# IceFeildBoard.net
KiCad netlist of a schematic drawn in EAGLE
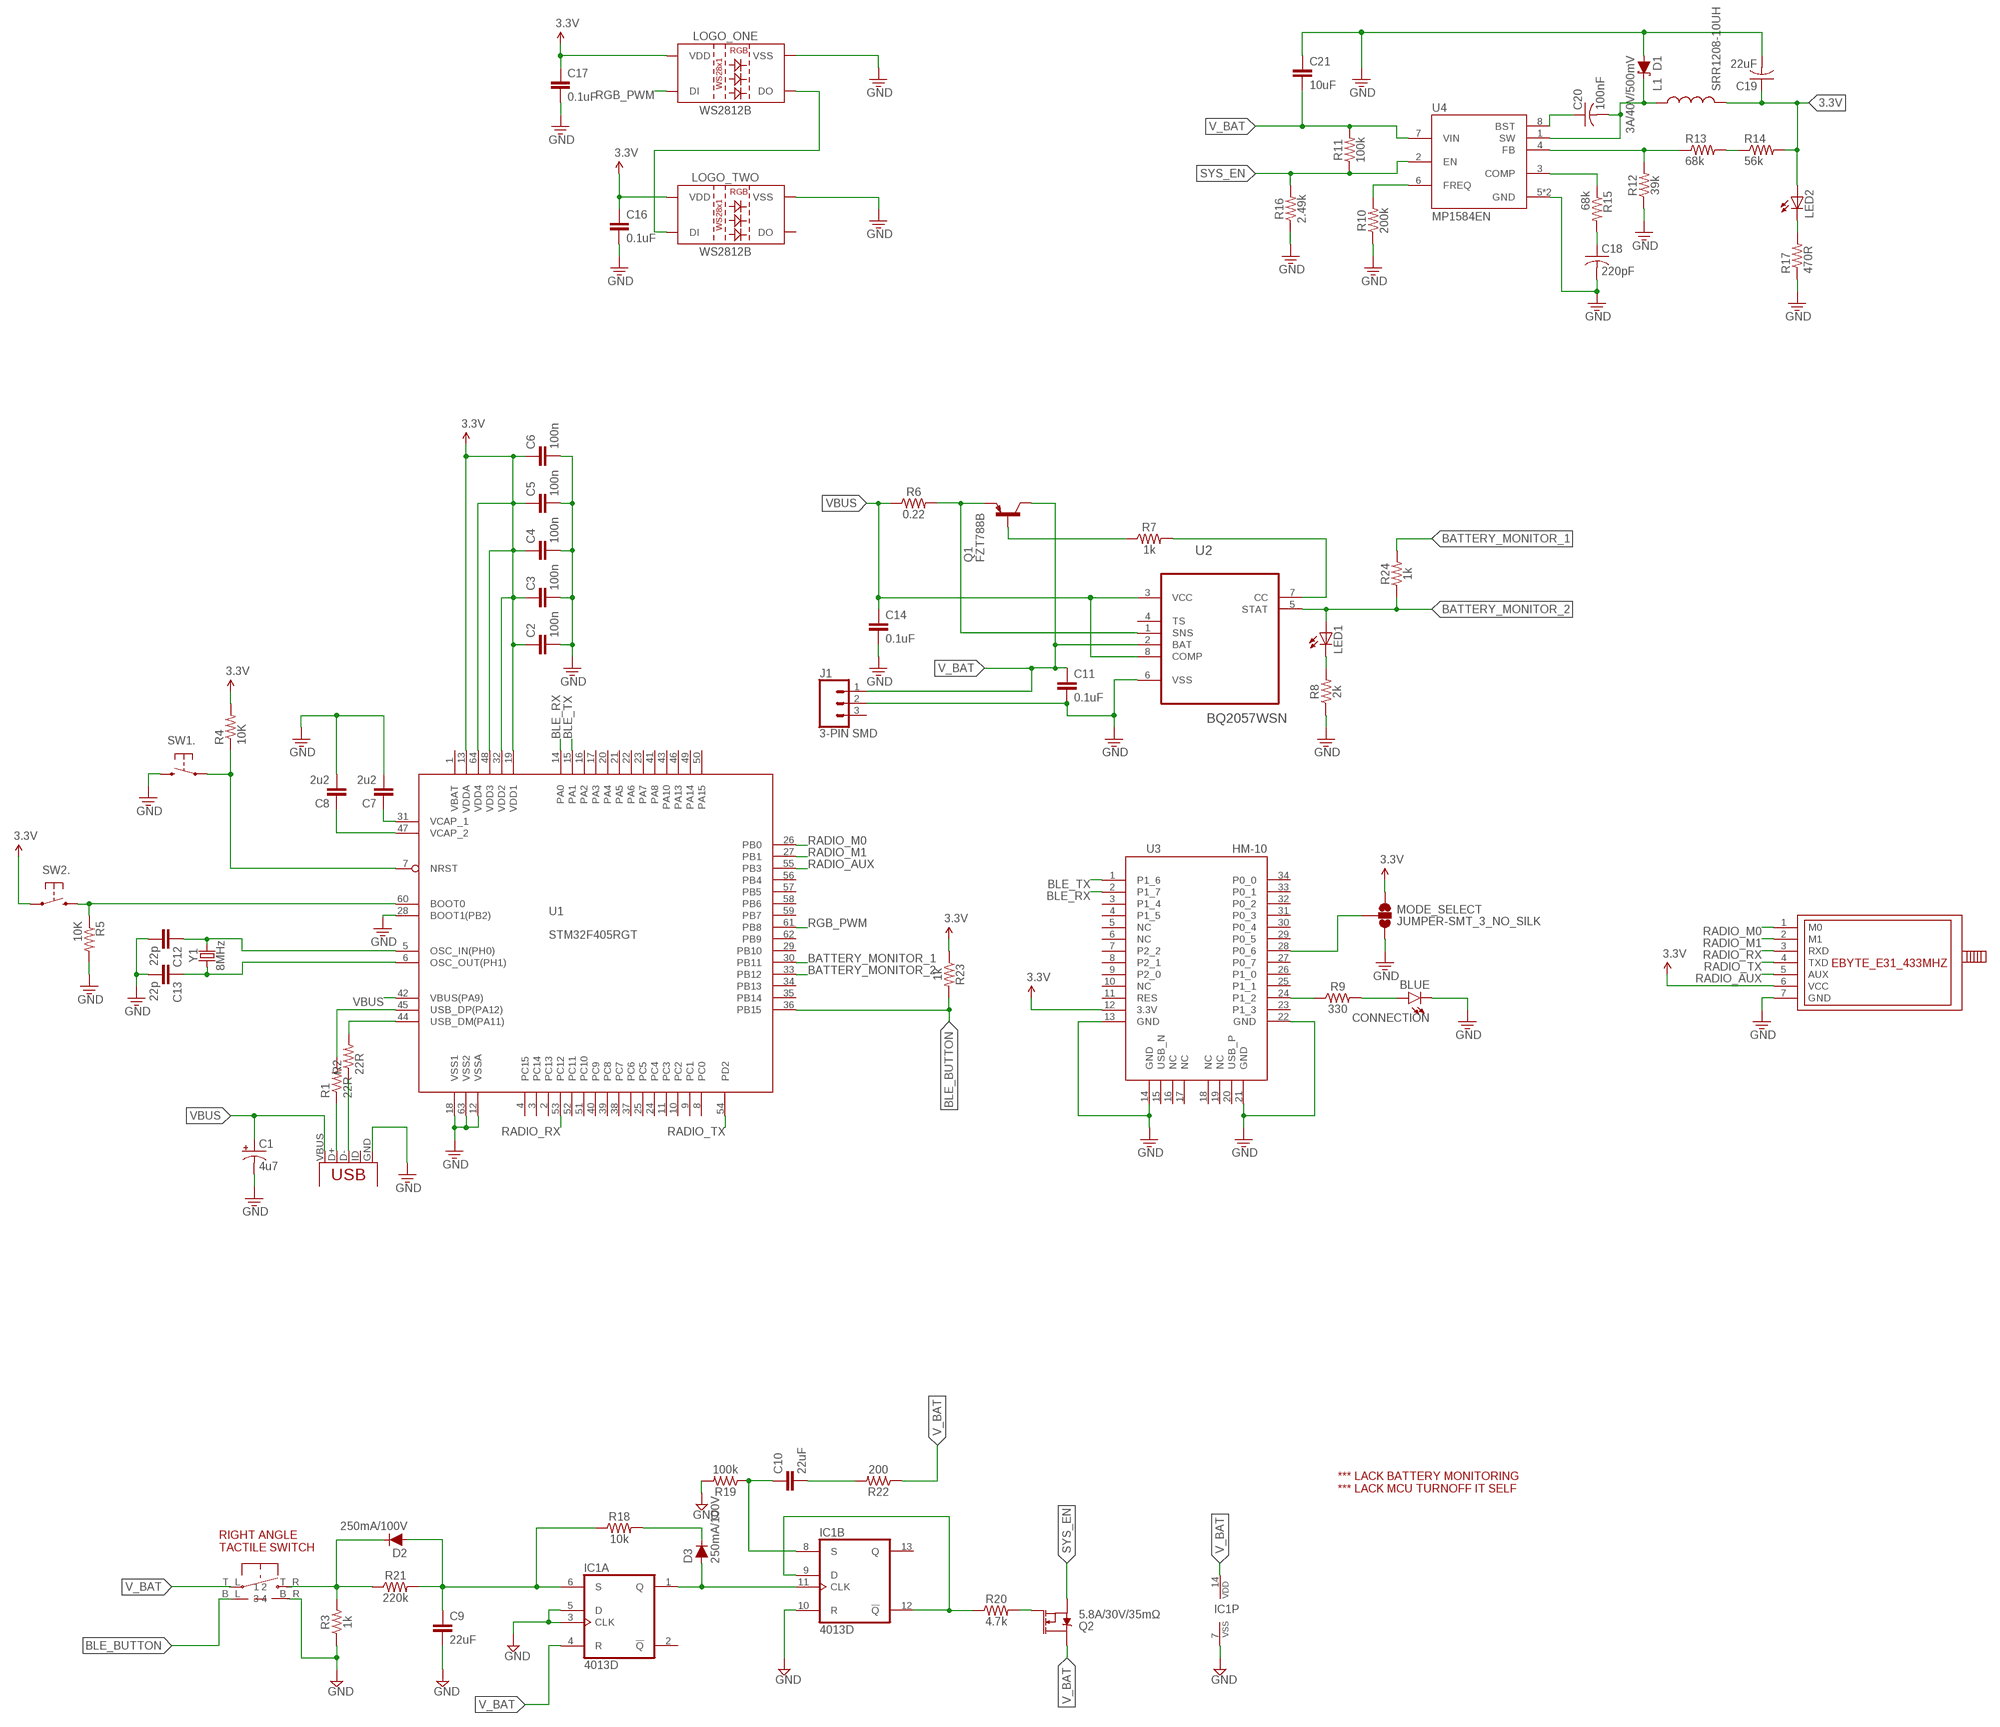
[diagram p0: schematic, sheet 1]

(export (version "E")
  (design (tool "Eeschema 10.0.6"))
  (components
    (comp (ref "C1")
      (value "4u7")
      (footprint "eagle-import:EIA3216-KIT")
      (libsource (lib "eagle-import") (part "CAP_POL1206-KIT"))
    )
    (comp (ref "C2")
      (value "100n")
      (footprint "eagle-import:0603-CAP")
      (libsource (lib "eagle-import") (part "CAP0603-CAP"))
    )
    (comp (ref "C3")
      (value "100n")
      (footprint "eagle-import:0603-CAP")
      (libsource (lib "eagle-import") (part "CAP0603-CAP"))
    )
    (comp (ref "C4")
      (value "100n")
      (footprint "eagle-import:0603-CAP")
      (libsource (lib "eagle-import") (part "CAP0603-CAP"))
    )
    (comp (ref "C5")
      (value "100n")
      (footprint "eagle-import:0603-CAP")
      (libsource (lib "eagle-import") (part "CAP0603-CAP"))
    )
    (comp (ref "C6")
      (value "100n")
      (footprint "eagle-import:0603-CAP")
      (libsource (lib "eagle-import") (part "CAP0603-CAP"))
    )
    (comp (ref "C7")
      (value "2u2")
      (footprint "eagle-import:0603-CAP")
      (libsource (lib "eagle-import") (part "CAP0603-CAP"))
    )
    (comp (ref "C8")
      (value "2u2")
      (footprint "eagle-import:0603-CAP")
      (libsource (lib "eagle-import") (part "CAP0603-CAP"))
    )
    (comp (ref "C9")
      (value "22uF")
      (footprint "eagle-import:0805")
      (libsource (lib "eagle-import") (part "22UF-0805-6.3V-20%"))
    )
    (comp (ref "C10")
      (value "22uF")
      (footprint "eagle-import:0805")
      (libsource (lib "eagle-import") (part "22UF-0805-6.3V-20%"))
    )
    (comp (ref "C11")
      (value "0.1uF")
      (footprint "eagle-import:0603")
      (libsource (lib "eagle-import") (part "0.1UF-0603-25V-(+80/-20%)"))
    )
    (comp (ref "C12")
      (value "22p")
      (footprint "eagle-import:0603-CAP")
      (libsource (lib "eagle-import") (part "CAP0603-CAP"))
    )
    (comp (ref "C13")
      (value "22p")
      (footprint "eagle-import:0603-CAP")
      (libsource (lib "eagle-import") (part "CAP0603-CAP"))
    )
    (comp (ref "C14")
      (value "0.1uF")
      (footprint "eagle-import:0603")
      (libsource (lib "eagle-import") (part "0.1UF-0603-25V-(+80/-20%)"))
    )
    (comp (ref "C16")
      (value "0.1uF")
      (footprint "eagle-import:0603")
      (libsource (lib "eagle-import") (part "0.1UF-0603-25V-5%"))
    )
    (comp (ref "C17")
      (value "0.1uF")
      (footprint "eagle-import:0603")
      (libsource (lib "eagle-import") (part "0.1UF-0603-25V-5%"))
    )
    (comp (ref "C18")
      (value "220pF")
      (footprint "eagle-import:C0603")
      (libsource (lib "eagle-import") (part "C-USC0603"))
    )
    (comp (ref "C19")
      (value "22uF")
      (footprint "eagle-import:C0603")
      (libsource (lib "eagle-import") (part "C-USC0603"))
    )
    (comp (ref "C20")
      (value "100nF")
      (footprint "eagle-import:C0603")
      (libsource (lib "eagle-import") (part "C-USC0603"))
    )
    (comp (ref "C21")
      (value "10uF")
      (footprint "eagle-import:0603")
      (libsource (lib "eagle-import") (part "10UF-0603-6.3V-20%"))
    )
    (comp (ref "CONNECTION")
      (value "BLUE")
      (footprint "eagle-import:LED-0603")
      (libsource (lib "eagle-import") (part "LED-BLUE0603"))
    )
    (comp (ref "D1")
      (value "3A/40V/500mV")
      (footprint "eagle-import:SMA-DIODE")
      (libsource (lib "eagle-import") (part "DIODE-SCHOTTKY-B340A"))
    )
    (comp (ref "D2")
      (value "250mA/100V")
      (footprint "eagle-import:SOD-323")
      (libsource (lib "eagle-import") (part "DIODE-BAS16J"))
    )
    (comp (ref "D3")
      (value "250mA/100V")
      (footprint "eagle-import:SOD-323")
      (libsource (lib "eagle-import") (part "DIODE-BAS16J"))
    )
    (comp (ref "IC1")
      (value "4013D")
      (footprint "eagle-import:SO14")
      (fields (field (name "OC_NEWARK") "unknown"))
      (libsource (lib "eagle-import") (part "4013D"))
    )
    (comp (ref "J1")
      (value "3-PIN SMD")
      (footprint "eagle-import:JST-3-SMD")
      (libsource (lib "eagle-import") (part "CONN_03JST-SMD"))
    )
    (comp (ref "L1")
      (value "SRR1208-10UH")
      (footprint "eagle-import:1008")
      (libsource (lib "eagle-import") (part "SRR1208-10UH"))
    )
    (comp (ref "LED1")
      (value "LED0603")
      (footprint "eagle-import:LED-0603")
      (libsource (lib "eagle-import") (part "LED0603"))
    )
    (comp (ref "LED2")
      (value "LED0603")
      (footprint "eagle-import:LED-0603")
      (libsource (lib "eagle-import") (part "LED0603"))
    )
    (comp (ref "LOGO_ONE")
      (value "WS2812B")
      (footprint "eagle-import:WS2812B")
      (libsource (lib "eagle-import") (part "WS2812B"))
    )
    (comp (ref "LOGO_TWO")
      (value "WS2812B")
      (footprint "eagle-import:WS2812B")
      (libsource (lib "eagle-import") (part "WS2812B"))
    )
    (comp (ref "MODE_SELECT")
      (value "JUMPER-SMT_3_NO_SILK")
      (footprint "eagle-import:SMT-JUMPER_3_NO_SILK")
      (libsource (lib "eagle-import") (part "JUMPER-SMT_3_NO_SILK"))
    )
    (comp (ref "Q1")
      (value "FZT788B")
      (footprint "eagle-import:SOT230P700X180-4N")
      (libsource (lib "eagle-import") (part "FZT788B"))
    )
    (comp (ref "Q2")
      (value "5.8A/30V/35mΩ")
      (footprint "eagle-import:SOT23-3")
      (libsource (lib "eagle-import") (part "MOSFET-NCH-AO3404A"))
    )
    (comp (ref "R1")
      (value "22R")
      (footprint "eagle-import:0603-RES")
      (libsource (lib "eagle-import") (part "RESISTOR0603-RES"))
    )
    (comp (ref "R2")
      (value "22R")
      (footprint "eagle-import:0603-RES")
      (libsource (lib "eagle-import") (part "RESISTOR0603-RES"))
    )
    (comp (ref "R3")
      (value "1k")
      (footprint "eagle-import:0603")
      (libsource (lib "eagle-import") (part "1KOHM-0603-1/10W-1%"))
    )
    (comp (ref "R4")
      (value "10K")
      (footprint "eagle-import:0603-RES")
      (libsource (lib "eagle-import") (part "RESISTOR0603-RES"))
    )
    (comp (ref "R5")
      (value "10K")
      (footprint "eagle-import:0603-RES")
      (libsource (lib "eagle-import") (part "RESISTOR0603-RES"))
    )
    (comp (ref "R6")
      (value "0.22")
      (footprint "eagle-import:0805")
      (libsource (lib "eagle-import") (part "0.22OHM-0805-1/4W-1%"))
    )
    (comp (ref "R7")
      (value "1k")
      (footprint "eagle-import:0603")
      (libsource (lib "eagle-import") (part "1KOHM-0603-1/10W-1%"))
    )
    (comp (ref "R8")
      (value "2k")
      (footprint "eagle-import:0603")
      (libsource (lib "eagle-import") (part "RESISTOR0603"))
    )
    (comp (ref "R9")
      (value "330")
      (footprint "eagle-import:0603")
      (libsource (lib "eagle-import") (part "330OHM-0603-1/10W-1%"))
    )
    (comp (ref "R10")
      (value "200k")
      (footprint "eagle-import:0603")
      (libsource (lib "eagle-import") (part "200KOHM-0603-1/10W-1%"))
    )
    (comp (ref "R11")
      (value "100k")
      (footprint "eagle-import:0603")
      (libsource (lib "eagle-import") (part "100KOHM-0603-1/10W-1%"))
    )
    (comp (ref "R12")
      (value "39k")
      (footprint "eagle-import:0603")
      (libsource (lib "eagle-import") (part "39KOHM-0603-1/10W-1%"))
    )
    (comp (ref "R13")
      (value "68k")
      (footprint "eagle-import:R0603")
      (libsource (lib "eagle-import") (part "R-US_R0603"))
    )
    (comp (ref "R14")
      (value "56k")
      (footprint "eagle-import:R0603")
      (libsource (lib "eagle-import") (part "R-US_R0603"))
    )
    (comp (ref "R15")
      (value "68k")
      (footprint "eagle-import:R0603")
      (libsource (lib "eagle-import") (part "R-US_R0603"))
    )
    (comp (ref "R16")
      (value "2.49k")
      (footprint "eagle-import:0603")
      (libsource (lib "eagle-import") (part "2.49KOHM-0603-1/10W-1%"))
    )
    (comp (ref "R17")
      (value "470R")
      (footprint "eagle-import:0603-RES")
      (libsource (lib "eagle-import") (part "RESISTOR0603-RES"))
    )
    (comp (ref "R18")
      (value "10k")
      (footprint "eagle-import:0603")
      (libsource (lib "eagle-import") (part "10KOHM-0603-1/10W-1%"))
    )
    (comp (ref "R19")
      (value "100k")
      (footprint "eagle-import:0603")
      (libsource (lib "eagle-import") (part "100KOHM-0603-1/10W-1%"))
    )
    (comp (ref "R20")
      (value "4.7k")
      (footprint "eagle-import:0603")
      (libsource (lib "eagle-import") (part "4.7KOHM-0603-1/10W-1%"))
    )
    (comp (ref "R21")
      (value "220k")
      (footprint "eagle-import:0603")
      (libsource (lib "eagle-import") (part "220KOHM-0603-1/10W-1%"))
    )
    (comp (ref "R22")
      (value "200")
      (footprint "eagle-import:0603")
      (libsource (lib "eagle-import") (part "200OHM-0603-1/10W-1%"))
    )
    (comp (ref "R23")
      (value "1k")
      (footprint "eagle-import:0603")
      (libsource (lib "eagle-import") (part "1KOHM-0603-1/10W-1%"))
    )
    (comp (ref "R24")
      (value "1k")
      (footprint "eagle-import:0603")
      (libsource (lib "eagle-import") (part "1KOHM-0603-1/10W-1%"))
    )
    (comp (ref "SW1")
      (value "!RST")
      (footprint "eagle-import:SWITCH-TACT-B3U-1100P-B")
      (libsource (lib "eagle-import") (part "SWITCH-B3U-1110-BOSS"))
    )
    (comp (ref "SW2")
      (value "BOOT")
      (footprint "eagle-import:SWITCH-TACT-B3U-1100P-B")
      (libsource (lib "eagle-import") (part "SWITCH-B3U-1110-BOSS"))
    )
    (comp (ref "U$1")
      (value "RIGHT_ANGLE_TACTILE_SWITCH")
      (footprint "eagle-import:RIGHT_ANGLE_TACTILE_SWITCH")
      (libsource (lib "eagle-import") (part "RIGHT_ANGLE_TACTILE_SWITCH"))
    )
    (comp (ref "U$2")
      (value "EBYTE_E31_433MHZ")
      (footprint "eagle-import:EBYTE_E31_433MHZ")
      (libsource (lib "eagle-import") (part "EBYTE_E31_433MHZ"))
    )
    (comp (ref "U1")
      (value "STM32F405RGT")
      (footprint "eagle-import:LQFP64")
      (libsource (lib "eagle-import") (part "STM32F405RGT"))
    )
    (comp (ref "U2")
      (value "BQ2057WSN")
      (footprint "eagle-import:SOIC127P600X175-8N")
      (fields (field (name "MF") "Texas Instruments"))
      (libsource (lib "eagle-import") (part "BQ2057WSN"))
    )
    (comp (ref "U3")
      (value "HM-10")
      (footprint "eagle-import:HM-10")
      (libsource (lib "eagle-import") (part "HM-10"))
    )
    (comp (ref "U4")
      (value "MP1584EN")
      (footprint "eagle-import:SOIC9P127_490X600X170L84X42T330X241N")
      (fields (field (name "MF") "Monolithic Power Systems"))
      (libsource (lib "eagle-import") (part "MP1584EN"))
    )
    (comp (ref "USB")
      (value "USB-MICROB-SMD")
      (footprint "eagle-import:USB-MICROB-SMD")
      (libsource (lib "eagle-import") (part "USB-MICROB-SMD"))
    )
    (comp (ref "Y1")
      (value "8MHz")
      (footprint "eagle-import:CRYSTAL-SMD-5X3.2-4PAD")
      (libsource (lib "eagle-import") (part "CRYSTAL-8MHZSMD-5X3.2"))
    )
  )
  (nets
    (net (code "1") (name "/BLE_RX") (class "Default")
      (node (ref "U1") (pin "14") (pinfunction "PA0_14") (pintype "bidirectional"))
      (node (ref "U3") (pin "2") (pinfunction "P1_7_2") (pintype "bidirectional"))
    )
    (net (code "2") (name "/BLE_TX") (class "Default")
      (node (ref "U1") (pin "15") (pinfunction "PA1_15") (pintype "bidirectional"))
      (node (ref "U3") (pin "1") (pinfunction "P1_6_1") (pintype "bidirectional"))
    )
    (net (code "3") (name "/RADIO_AUX") (class "Default")
      (node (ref "U$2") (pin "5") (pinfunction "AUX_5") (pintype "bidirectional"))
      (node (ref "U1") (pin "55") (pinfunction "PB3_55") (pintype "bidirectional"))
    )
    (net (code "4") (name "/RADIO_M0") (class "Default")
      (node (ref "U$2") (pin "1") (pinfunction "M0_1") (pintype "bidirectional"))
      (node (ref "U1") (pin "26") (pinfunction "PB0_26") (pintype "bidirectional"))
    )
    (net (code "5") (name "/RADIO_M1") (class "Default")
      (node (ref "U$2") (pin "2") (pinfunction "M1_2") (pintype "bidirectional"))
      (node (ref "U1") (pin "27") (pinfunction "PB1_27") (pintype "bidirectional"))
    )
    (net (code "6") (name "/RADIO_RX") (class "Default")
      (node (ref "U$2") (pin "3") (pinfunction "RXD_3") (pintype "bidirectional"))
      (node (ref "U1") (pin "53") (pinfunction "PC12_53") (pintype "bidirectional"))
    )
    (net (code "7") (name "/RADIO_TX") (class "Default")
      (node (ref "U$2") (pin "4") (pinfunction "TXD_4") (pintype "bidirectional"))
      (node (ref "U1") (pin "54") (pinfunction "PD2_54") (pintype "bidirectional"))
    )
    (net (code "8") (name "/RGB_PWM") (class "Default")
      (node (ref "LOGO_ONE") (pin "4") (pinfunction "DI_4") (pintype "bidirectional"))
      (node (ref "U1") (pin "61") (pinfunction "PB8_61") (pintype "bidirectional"))
    )
    (net (code "9") (name "/VBAT") (class "Default")
      (node (ref "U1") (pin "1") (pinfunction "VBAT_1") (pintype "power_in"))
    )
    (net (code "10") (name "3.3V") (class "Default")
      (node (ref "C16") (pin "1") (pinfunction "1_1") (pintype "passive"))
      (node (ref "C17") (pin "1") (pinfunction "1_1") (pintype "passive"))
      (node (ref "C19") (pin "1") (pinfunction "1_1") (pintype "passive"))
      (node (ref "C2") (pin "1") (pinfunction "1_1") (pintype "passive"))
      (node (ref "C3") (pin "1") (pinfunction "1_1") (pintype "passive"))
      (node (ref "C4") (pin "1") (pinfunction "1_1") (pintype "passive"))
      (node (ref "C5") (pin "1") (pinfunction "1_1") (pintype "passive"))
      (node (ref "C6") (pin "1") (pinfunction "1_1") (pintype "passive"))
      (node (ref "L1") (pin "2") (pinfunction "2_2") (pintype "passive"))
      (node (ref "LED2") (pin "A") (pinfunction "A_A") (pintype "passive"))
      (node (ref "LOGO_ONE") (pin "1") (pinfunction "VDD_1") (pintype "bidirectional"))
      (node (ref "LOGO_TWO") (pin "1") (pinfunction "VDD_1") (pintype "bidirectional"))
      (node (ref "MODE_SELECT") (pin "1") (pinfunction "1_1") (pintype "passive"))
      (node (ref "R14") (pin "2") (pinfunction "2_2") (pintype "passive"))
      (node (ref "R23") (pin "1") (pinfunction "1_1") (pintype "passive"))
      (node (ref "R4") (pin "2") (pinfunction "2_2") (pintype "passive"))
      (node (ref "SW2") (pin "1") (pinfunction "1_1") (pintype "passive"))
      (node (ref "U$2") (pin "6") (pinfunction "VCC_6") (pintype "bidirectional"))
      (node (ref "U1") (pin "13") (pinfunction "VDDA_13") (pintype "power_in"))
      (node (ref "U1") (pin "19") (pinfunction "VDD1_19") (pintype "power_in"))
      (node (ref "U1") (pin "32") (pinfunction "VDD2_32") (pintype "power_in"))
      (node (ref "U1") (pin "48") (pinfunction "VDD3_48") (pintype "power_in"))
      (node (ref "U1") (pin "64") (pinfunction "VDD4_64") (pintype "power_in"))
      (node (ref "U3") (pin "12") (pinfunction "3.3V_12") (pintype "bidirectional"))
    )
    (net (code "11") (name "BATTERY_MONITOR_1") (class "Default")
      (node (ref "R24") (pin "2") (pinfunction "2_2") (pintype "passive"))
      (node (ref "U1") (pin "30") (pinfunction "PB11_30") (pintype "bidirectional"))
    )
    (net (code "12") (name "BATTERY_MONITOR_2") (class "Default")
      (node (ref "LED1") (pin "A") (pinfunction "A_A") (pintype "passive"))
      (node (ref "R24") (pin "1") (pinfunction "1_1") (pintype "passive"))
      (node (ref "U1") (pin "33") (pinfunction "PB12_33") (pintype "bidirectional"))
      (node (ref "U2") (pin "5") (pinfunction "STAT_5") (pintype "output"))
    )
    (net (code "13") (name "BLE_BUTTON") (class "Default")
      (node (ref "R23") (pin "2") (pinfunction "2_2") (pintype "passive"))
      (node (ref "U$1") (pin "B_L") (pinfunction "3_B_L") (pintype "bidirectional"))
      (node (ref "U1") (pin "36") (pinfunction "PB15_36") (pintype "bidirectional"))
    )
    (net (code "14") (name "GND") (class "Default")
      (node (ref "C1") (pin "C") (pinfunction "-_C") (pintype "passive"))
      (node (ref "C11") (pin "2") (pinfunction "2_2") (pintype "passive"))
      (node (ref "C12") (pin "2") (pinfunction "2_2") (pintype "passive"))
      (node (ref "C13") (pin "2") (pinfunction "2_2") (pintype "passive"))
      (node (ref "C14") (pin "2") (pinfunction "2_2") (pintype "passive"))
      (node (ref "C16") (pin "2") (pinfunction "2_2") (pintype "passive"))
      (node (ref "C17") (pin "2") (pinfunction "2_2") (pintype "passive"))
      (node (ref "C18") (pin "2") (pinfunction "2_2") (pintype "passive"))
      (node (ref "C19") (pin "2") (pinfunction "2_2") (pintype "passive"))
      (node (ref "C2") (pin "2") (pinfunction "2_2") (pintype "passive"))
      (node (ref "C21") (pin "1") (pinfunction "1_1") (pintype "passive"))
      (node (ref "C3") (pin "2") (pinfunction "2_2") (pintype "passive"))
      (node (ref "C4") (pin "2") (pinfunction "2_2") (pintype "passive"))
      (node (ref "C5") (pin "2") (pinfunction "2_2") (pintype "passive"))
      (node (ref "C6") (pin "2") (pinfunction "2_2") (pintype "passive"))
      (node (ref "C7") (pin "2") (pinfunction "2_2") (pintype "passive"))
      (node (ref "C8") (pin "2") (pinfunction "2_2") (pintype "passive"))
      (node (ref "C9") (pin "2") (pinfunction "2_2") (pintype "passive"))
      (node (ref "CONNECTION") (pin "C") (pinfunction "C_C") (pintype "passive"))
      (node (ref "D1") (pin "A") (pinfunction "A_A") (pintype "passive"))
      (node (ref "IC1") (pin "10") (pinfunction "R_10") (pintype "input"))
      (node (ref "IC1") (pin "3") (pinfunction "CLK_3") (pintype "input"))
      (node (ref "IC1") (pin "5") (pinfunction "D_5") (pintype "input"))
      (node (ref "IC1") (pin "7") (pinfunction "VSS_7") (pintype "power_in"))
      (node (ref "J1") (pin "2") (pinfunction "2_2") (pintype "passive"))
      (node (ref "LOGO_ONE") (pin "3") (pinfunction "VSS_3") (pintype "bidirectional"))
      (node (ref "LOGO_TWO") (pin "3") (pinfunction "VSS_3") (pintype "bidirectional"))
      (node (ref "MODE_SELECT") (pin "3") (pinfunction "3_3") (pintype "passive"))
      (node (ref "R10") (pin "1") (pinfunction "1_1") (pintype "passive"))
      (node (ref "R12") (pin "1") (pinfunction "1_1") (pintype "passive"))
      (node (ref "R16") (pin "1") (pinfunction "1_1") (pintype "passive"))
      (node (ref "R17") (pin "1") (pinfunction "1_1") (pintype "passive"))
      (node (ref "R19") (pin "2") (pinfunction "2_2") (pintype "passive"))
      (node (ref "R3") (pin "1") (pinfunction "1_1") (pintype "passive"))
      (node (ref "R5") (pin "2") (pinfunction "2_2") (pintype "passive"))
      (node (ref "R8") (pin "1") (pinfunction "1_1") (pintype "passive"))
      (node (ref "SW1") (pin "2") (pinfunction "2_2") (pintype "passive"))
      (node (ref "U$1") (pin "B_R") (pinfunction "4_B_R") (pintype "bidirectional"))
      (node (ref "U$2") (pin "7") (pinfunction "GND_7") (pintype "bidirectional"))
      (node (ref "U1") (pin "12") (pinfunction "VSSA_12") (pintype "power_in"))
      (node (ref "U1") (pin "18") (pinfunction "VSS1_18") (pintype "power_in"))
      (node (ref "U1") (pin "28") (pinfunction "BOOT1(PB2)_28") (pintype "input"))
      (node (ref "U1") (pin "63") (pinfunction "VSS2_63") (pintype "power_in"))
      (node (ref "U2") (pin "6") (pinfunction "VSS_6") (pintype "power_in"))
      (node (ref "U3") (pin "13") (pinfunction "GND_13") (pintype "bidirectional"))
      (node (ref "U3") (pin "14") (pinfunction "GND_14") (pintype "bidirectional"))
      (node (ref "U3") (pin "21") (pinfunction "GND_21") (pintype "bidirectional"))
      (node (ref "U3") (pin "22") (pinfunction "GND_22") (pintype "bidirectional"))
      (node (ref "U4") (pin "5") (pinfunction "GND_5") (pintype "power_in"))
      (node (ref "U4") (pin "9") (pinfunction "GND_9") (pintype "power_in"))
      (node (ref "USB") (pin "GND") (pinfunction "GND_GND") (pintype "bidirectional"))
    )
    (net (code "15") (name "Net-(C10-Pad2)") (class "Default")
      (node (ref "C10") (pin "2") (pinfunction "2_2") (pintype "passive"))
      (node (ref "R22") (pin "2") (pinfunction "2_2") (pintype "passive"))
    )
    (net (code "16") (name "Net-(C18-Pad1)") (class "Default")
      (node (ref "C18") (pin "1") (pinfunction "1_1") (pintype "passive"))
      (node (ref "R15") (pin "2") (pinfunction "2_2") (pintype "passive"))
    )
    (net (code "17") (name "Net-(CONNECTION-PadA)") (class "Default")
      (node (ref "CONNECTION") (pin "A") (pinfunction "A_A") (pintype "passive"))
      (node (ref "R9") (pin "2") (pinfunction "2_2") (pintype "passive"))
    )
    (net (code "18") (name "Net-(D3-PadC)") (class "Default")
      (node (ref "D3") (pin "C") (pinfunction "C_C") (pintype "passive"))
      (node (ref "R18") (pin "2") (pinfunction "2_2") (pintype "passive"))
    )
    (net (code "19") (name "Net-(IC1A-Q)") (class "Default")
      (node (ref "D3") (pin "A") (pinfunction "A_A") (pintype "passive"))
      (node (ref "IC1") (pin "1") (pinfunction "Q_1") (pintype "output"))
      (node (ref "IC1") (pin "11") (pinfunction "CLK_11") (pintype "input"))
    )
    (net (code "20") (name "Net-(IC1A-S)") (class "Default")
      (node (ref "C9") (pin "1") (pinfunction "1_1") (pintype "passive"))
      (node (ref "D2") (pin "A") (pinfunction "A_A") (pintype "passive"))
      (node (ref "IC1") (pin "6") (pinfunction "S_6") (pintype "input"))
      (node (ref "R18") (pin "1") (pinfunction "1_1") (pintype "passive"))
      (node (ref "R21") (pin "2") (pinfunction "2_2") (pintype "passive"))
    )
    (net (code "21") (name "Net-(IC1B-D)") (class "Default")
      (node (ref "IC1") (pin "12") (pinfunction "~{Q}_12") (pintype "output"))
      (node (ref "IC1") (pin "9") (pinfunction "D_9") (pintype "input"))
      (node (ref "R20") (pin "1") (pinfunction "1_1") (pintype "passive"))
    )
    (net (code "22") (name "Net-(IC1B-S)") (class "Default")
      (node (ref "C10") (pin "1") (pinfunction "1_1") (pintype "passive"))
      (node (ref "IC1") (pin "8") (pinfunction "S_8") (pintype "input"))
      (node (ref "R19") (pin "1") (pinfunction "1_1") (pintype "passive"))
    )
    (net (code "23") (name "Net-(LED1-PadC)") (class "Default")
      (node (ref "LED1") (pin "C") (pinfunction "C_C") (pintype "passive"))
      (node (ref "R8") (pin "2") (pinfunction "2_2") (pintype "passive"))
    )
    (net (code "24") (name "Net-(LED2-PadC)") (class "Default")
      (node (ref "LED2") (pin "C") (pinfunction "C_C") (pintype "passive"))
      (node (ref "R17") (pin "2") (pinfunction "2_2") (pintype "passive"))
    )
    (net (code "25") (name "Net-(LOGO_ONE-DO)") (class "Default")
      (node (ref "LOGO_ONE") (pin "2") (pinfunction "DO_2") (pintype "bidirectional"))
      (node (ref "LOGO_TWO") (pin "4") (pinfunction "DI_4") (pintype "bidirectional"))
    )
    (net (code "26") (name "Net-(Q1-B)") (class "Default")
      (node (ref "Q1") (pin "1") (pinfunction "B_1") (pintype "passive"))
      (node (ref "R7") (pin "1") (pinfunction "1_1") (pintype "passive"))
    )
    (net (code "27") (name "Net-(Q1-E)") (class "Default")
      (node (ref "Q1") (pin "3") (pinfunction "E_3") (pintype "passive"))
      (node (ref "R6") (pin "2") (pinfunction "2_2") (pintype "passive"))
      (node (ref "U2") (pin "1") (pinfunction "SNS_1") (pintype "input"))
    )
    (net (code "28") (name "Net-(Q2-G)") (class "Default")
      (node (ref "Q2") (pin "1") (pinfunction "G_1") (pintype "bidirectional"))
      (node (ref "R20") (pin "2") (pinfunction "2_2") (pintype "passive"))
    )
    (net (code "29") (name "Net-(R1-Pad1)") (class "Default")
      (node (ref "R1") (pin "1") (pinfunction "1_1") (pintype "passive"))
      (node (ref "USB") (pin "D+") (pinfunction "D+_D+") (pintype "bidirectional"))
    )
    (net (code "30") (name "Net-(R2-Pad1)") (class "Default")
      (node (ref "R2") (pin "1") (pinfunction "1_1") (pintype "passive"))
      (node (ref "USB") (pin "D-") (pinfunction "D-_D-") (pintype "bidirectional"))
    )
    (net (code "31") (name "Net-(R13-Pad2)") (class "Default")
      (node (ref "R13") (pin "2") (pinfunction "2_2") (pintype "passive"))
      (node (ref "R14") (pin "1") (pinfunction "1_1") (pintype "passive"))
    )
    (net (code "32") (name "Net-(U$1-2)") (class "Default")
      (node (ref "D2") (pin "C") (pinfunction "C_C") (pintype "passive"))
      (node (ref "R21") (pin "1") (pinfunction "1_1") (pintype "passive"))
      (node (ref "R3") (pin "2") (pinfunction "2_2") (pintype "passive"))
      (node (ref "U$1") (pin "T_R") (pinfunction "2_T_R") (pintype "bidirectional"))
    )
    (net (code "33") (name "Net-(U1-BOOT0)") (class "Default")
      (node (ref "R5") (pin "1") (pinfunction "1_1") (pintype "passive"))
      (node (ref "SW2") (pin "2") (pinfunction "2_2") (pintype "passive"))
      (node (ref "U1") (pin "60") (pinfunction "BOOT0_60") (pintype "input"))
    )
    (net (code "34") (name "Net-(U1-NRST)") (class "Default")
      (node (ref "R4") (pin "1") (pinfunction "1_1") (pintype "passive"))
      (node (ref "SW1") (pin "1") (pinfunction "1_1") (pintype "passive"))
      (node (ref "U1") (pin "7") (pinfunction "NRST_7") (pintype "input"))
    )
    (net (code "35") (name "Net-(U1-OSC_IN(PH0))") (class "Default")
      (node (ref "C12") (pin "1") (pinfunction "1_1") (pintype "passive"))
      (node (ref "U1") (pin "5") (pinfunction "OSC_IN(PH0)_5") (pintype "bidirectional"))
      (node (ref "Y1") (pin "3") (pinfunction "2_3") (pintype "passive"))
    )
    (net (code "36") (name "Net-(U1-OSC_OUT(PH1))") (class "Default")
      (node (ref "C13") (pin "1") (pinfunction "1_1") (pintype "passive"))
      (node (ref "U1") (pin "6") (pinfunction "OSC_OUT(PH1)_6") (pintype "bidirectional"))
      (node (ref "Y1") (pin "1") (pinfunction "1_1") (pintype "passive"))
    )
    (net (code "37") (name "Net-(U1-USB_DM(PA11))") (class "Default")
      (node (ref "R2") (pin "2") (pinfunction "2_2") (pintype "passive"))
      (node (ref "U1") (pin "44") (pinfunction "USB_DM(PA11)_44") (pintype "bidirectional"))
    )
    (net (code "38") (name "Net-(U1-USB_DP(PA12))") (class "Default")
      (node (ref "R1") (pin "2") (pinfunction "2_2") (pintype "passive"))
      (node (ref "U1") (pin "45") (pinfunction "USB_DP(PA12)_45") (pintype "bidirectional"))
    )
    (net (code "39") (name "Net-(U1-VCAP_1)") (class "Default")
      (node (ref "C7") (pin "1") (pinfunction "1_1") (pintype "passive"))
      (node (ref "U1") (pin "31") (pinfunction "VCAP_1_31") (pintype "bidirectional"))
    )
    (net (code "40") (name "Net-(U1-VCAP_2)") (class "Default")
      (node (ref "C8") (pin "1") (pinfunction "1_1") (pintype "passive"))
      (node (ref "U1") (pin "47") (pinfunction "VCAP_2_47") (pintype "bidirectional"))
    )
    (net (code "41") (name "Net-(U2-CC)") (class "Default")
      (node (ref "R7") (pin "2") (pinfunction "2_2") (pintype "passive"))
      (node (ref "U2") (pin "7") (pinfunction "CC_7") (pintype "output"))
    )
    (net (code "42") (name "Net-(U2-COMP)") (class "Default")
      (node (ref "C14") (pin "1") (pinfunction "1_1") (pintype "passive"))
      (node (ref "R6") (pin "1") (pinfunction "1_1") (pintype "passive"))
      (node (ref "U2") (pin "3") (pinfunction "VCC_3") (pintype "power_in"))
      (node (ref "U2") (pin "8") (pinfunction "COMP_8") (pintype "input"))
    )
    (net (code "43") (name "Net-(U3-P0_6)") (class "Default")
      (node (ref "MODE_SELECT") (pin "2") (pinfunction "2_2") (pintype "passive"))
      (node (ref "U3") (pin "28") (pinfunction "P0_6_28") (pintype "bidirectional"))
    )
    (net (code "44") (name "Net-(U3-P1_2)") (class "Default")
      (node (ref "R9") (pin "1") (pinfunction "1_1") (pintype "passive"))
      (node (ref "U3") (pin "24") (pinfunction "P1_2_24") (pintype "bidirectional"))
    )
    (net (code "45") (name "Net-(U4-BST)") (class "Default")
      (node (ref "C20") (pin "1") (pinfunction "1_1") (pintype "passive"))
      (node (ref "U4") (pin "8") (pinfunction "BST_8") (pintype "passive"))
    )
    (net (code "46") (name "Net-(U4-COMP)") (class "Default")
      (node (ref "R15") (pin "1") (pinfunction "1_1") (pintype "passive"))
      (node (ref "U4") (pin "3") (pinfunction "COMP_3") (pintype "output"))
    )
    (net (code "47") (name "Net-(U4-FB)") (class "Default")
      (node (ref "R12") (pin "2") (pinfunction "2_2") (pintype "passive"))
      (node (ref "R13") (pin "1") (pinfunction "1_1") (pintype "passive"))
      (node (ref "U4") (pin "4") (pinfunction "FB_4") (pintype "input"))
    )
    (net (code "48") (name "Net-(U4-FREQ)") (class "Default")
      (node (ref "R10") (pin "2") (pinfunction "2_2") (pintype "passive"))
      (node (ref "U4") (pin "6") (pinfunction "FREQ_6") (pintype "input"))
    )
    (net (code "49") (name "Net-(U4-SW)") (class "Default")
      (node (ref "C20") (pin "2") (pinfunction "2_2") (pintype "passive"))
      (node (ref "D1") (pin "C") (pinfunction "C_C") (pintype "passive"))
      (node (ref "L1") (pin "1") (pinfunction "1_1") (pintype "passive"))
      (node (ref "U4") (pin "1") (pinfunction "SW_1") (pintype "output"))
    )
    (net (code "50") (name "SYS_EN") (class "Default")
      (node (ref "Q2") (pin "2") (pinfunction "S_2") (pintype "bidirectional"))
      (node (ref "R11") (pin "1") (pinfunction "1_1") (pintype "passive"))
      (node (ref "R16") (pin "2") (pinfunction "2_2") (pintype "passive"))
      (node (ref "U4") (pin "2") (pinfunction "EN_2") (pintype "input"))
    )
    (net (code "51") (name "VBUS") (class "Default")
      (node (ref "C1") (pin "A") (pinfunction "+_A") (pintype "passive"))
      (node (ref "U1") (pin "42") (pinfunction "VBUS(PA9)_42") (pintype "bidirectional"))
      (node (ref "USB") (pin "VBUS") (pinfunction "VBUS_VBUS") (pintype "bidirectional"))
    )
    (net (code "52") (name "V_BAT") (class "Default")
      (node (ref "C11") (pin "1") (pinfunction "1_1") (pintype "passive"))
      (node (ref "C21") (pin "2") (pinfunction "2_2") (pintype "passive"))
      (node (ref "IC1") (pin "14") (pinfunction "VDD_14") (pintype "power_in"))
      (node (ref "IC1") (pin "4") (pinfunction "R_4") (pintype "input"))
      (node (ref "J1") (pin "1") (pinfunction "3_1") (pintype "passive"))
      (node (ref "Q1") (pin "2") (pinfunction "C_2") (pintype "passive"))
      (node (ref "Q1") (pin "4") (pinfunction "C_4") (pintype "passive"))
      (node (ref "Q2") (pin "3") (pinfunction "D_3") (pintype "bidirectional"))
      (node (ref "R11") (pin "2") (pinfunction "2_2") (pintype "passive"))
      (node (ref "R22") (pin "1") (pinfunction "1_1") (pintype "passive"))
      (node (ref "U$1") (pin "T_L") (pinfunction "1_T_L") (pintype "bidirectional"))
      (node (ref "U2") (pin "2") (pinfunction "BAT_2") (pintype "input"))
      (node (ref "U4") (pin "7") (pinfunction "VIN_7") (pintype "input"))
    )
    (net (code "53") (name "unconnected-(IC1A-~{Q}-Pad2)") (class "Default")
      (node (ref "IC1") (pin "2") (pinfunction "~{Q}_2") (pintype "output"))
    )
    (net (code "54") (name "unconnected-(IC1B-Q-Pad13)") (class "Default")
      (node (ref "IC1") (pin "13") (pinfunction "Q_13") (pintype "output"))
    )
    (net (code "55") (name "unconnected-(J1-1-Pad3)") (class "Default")
      (node (ref "J1") (pin "3") (pinfunction "1_3") (pintype "passive"))
    )
    (net (code "56") (name "unconnected-(LOGO_TWO-DO-Pad2)") (class "Default")
      (node (ref "LOGO_TWO") (pin "2") (pinfunction "DO_2") (pintype "bidirectional"))
    )
    (net (code "57") (name "unconnected-(U1-PA2-Pad16)") (class "Default")
      (node (ref "U1") (pin "16") (pinfunction "PA2_16") (pintype "bidirectional"))
    )
    (net (code "58") (name "unconnected-(U1-PA3-Pad17)") (class "Default")
      (node (ref "U1") (pin "17") (pinfunction "PA3_17") (pintype "bidirectional"))
    )
    (net (code "59") (name "unconnected-(U1-PA4-Pad20)") (class "Default")
      (node (ref "U1") (pin "20") (pinfunction "PA4_20") (pintype "bidirectional"))
    )
    (net (code "60") (name "unconnected-(U1-PA5-Pad21)") (class "Default")
      (node (ref "U1") (pin "21") (pinfunction "PA5_21") (pintype "bidirectional"))
    )
    (net (code "61") (name "unconnected-(U1-PA6-Pad22)") (class "Default")
      (node (ref "U1") (pin "22") (pinfunction "PA6_22") (pintype "bidirectional"))
    )
    (net (code "62") (name "unconnected-(U1-PA7-Pad23)") (class "Default")
      (node (ref "U1") (pin "23") (pinfunction "PA7_23") (pintype "bidirectional"))
    )
    (net (code "63") (name "unconnected-(U1-PA8-Pad41)") (class "Default")
      (node (ref "U1") (pin "41") (pinfunction "PA8_41") (pintype "bidirectional"))
    )
    (net (code "64") (name "unconnected-(U1-PA10-Pad43)") (class "Default")
      (node (ref "U1") (pin "43") (pinfunction "PA10_43") (pintype "bidirectional"))
    )
    (net (code "65") (name "unconnected-(U1-PA13-Pad46)") (class "Default")
      (node (ref "U1") (pin "46") (pinfunction "PA13_46") (pintype "bidirectional"))
    )
    (net (code "66") (name "unconnected-(U1-PA14-Pad49)") (class "Default")
      (node (ref "U1") (pin "49") (pinfunction "PA14_49") (pintype "bidirectional"))
    )
    (net (code "67") (name "unconnected-(U1-PA15-Pad50)") (class "Default")
      (node (ref "U1") (pin "50") (pinfunction "PA15_50") (pintype "bidirectional"))
    )
    (net (code "68") (name "unconnected-(U1-PB4-Pad56)") (class "Default")
      (node (ref "U1") (pin "56") (pinfunction "PB4_56") (pintype "bidirectional"))
    )
    (net (code "69") (name "unconnected-(U1-PB5-Pad57)") (class "Default")
      (node (ref "U1") (pin "57") (pinfunction "PB5_57") (pintype "bidirectional"))
    )
    (net (code "70") (name "unconnected-(U1-PB6-Pad58)") (class "Default")
      (node (ref "U1") (pin "58") (pinfunction "PB6_58") (pintype "bidirectional"))
    )
    (net (code "71") (name "unconnected-(U1-PB7-Pad59)") (class "Default")
      (node (ref "U1") (pin "59") (pinfunction "PB7_59") (pintype "bidirectional"))
    )
    (net (code "72") (name "unconnected-(U1-PB9-Pad62)") (class "Default")
      (node (ref "U1") (pin "62") (pinfunction "PB9_62") (pintype "bidirectional"))
    )
    (net (code "73") (name "unconnected-(U1-PB10-Pad29)") (class "Default")
      (node (ref "U1") (pin "29") (pinfunction "PB10_29") (pintype "bidirectional"))
    )
    (net (code "74") (name "unconnected-(U1-PB13-Pad34)") (class "Default")
      (node (ref "U1") (pin "34") (pinfunction "PB13_34") (pintype "bidirectional"))
    )
    (net (code "75") (name "unconnected-(U1-PB14-Pad35)") (class "Default")
      (node (ref "U1") (pin "35") (pinfunction "PB14_35") (pintype "bidirectional"))
    )
    (net (code "76") (name "unconnected-(U1-PC0-Pad8)") (class "Default")
      (node (ref "U1") (pin "8") (pinfunction "PC0_8") (pintype "bidirectional"))
    )
    (net (code "77") (name "unconnected-(U1-PC1-Pad9)") (class "Default")
      (node (ref "U1") (pin "9") (pinfunction "PC1_9") (pintype "bidirectional"))
    )
    (net (code "78") (name "unconnected-(U1-PC2-Pad10)") (class "Default")
      (node (ref "U1") (pin "10") (pinfunction "PC2_10") (pintype "bidirectional"))
    )
    (net (code "79") (name "unconnected-(U1-PC3-Pad11)") (class "Default")
      (node (ref "U1") (pin "11") (pinfunction "PC3_11") (pintype "bidirectional"))
    )
    (net (code "80") (name "unconnected-(U1-PC4-Pad24)") (class "Default")
      (node (ref "U1") (pin "24") (pinfunction "PC4_24") (pintype "bidirectional"))
    )
    (net (code "81") (name "unconnected-(U1-PC5-Pad25)") (class "Default")
      (node (ref "U1") (pin "25") (pinfunction "PC5_25") (pintype "bidirectional"))
    )
    (net (code "82") (name "unconnected-(U1-PC6-Pad37)") (class "Default")
      (node (ref "U1") (pin "37") (pinfunction "PC6_37") (pintype "bidirectional"))
    )
    (net (code "83") (name "unconnected-(U1-PC7-Pad38)") (class "Default")
      (node (ref "U1") (pin "38") (pinfunction "PC7_38") (pintype "bidirectional"))
    )
    (net (code "84") (name "unconnected-(U1-PC8-Pad39)") (class "Default")
      (node (ref "U1") (pin "39") (pinfunction "PC8_39") (pintype "bidirectional"))
    )
    (net (code "85") (name "unconnected-(U1-PC9-Pad40)") (class "Default")
      (node (ref "U1") (pin "40") (pinfunction "PC9_40") (pintype "bidirectional"))
    )
    (net (code "86") (name "unconnected-(U1-PC10-Pad51)") (class "Default")
      (node (ref "U1") (pin "51") (pinfunction "PC10_51") (pintype "bidirectional"))
    )
    (net (code "87") (name "unconnected-(U1-PC11-Pad52)") (class "Default")
      (node (ref "U1") (pin "52") (pinfunction "PC11_52") (pintype "bidirectional"))
    )
    (net (code "88") (name "unconnected-(U1-PC13-Pad2)") (class "Default")
      (node (ref "U1") (pin "2") (pinfunction "PC13_2") (pintype "bidirectional"))
    )
    (net (code "89") (name "unconnected-(U1-PC14-Pad3)") (class "Default")
      (node (ref "U1") (pin "3") (pinfunction "PC14_3") (pintype "bidirectional"))
    )
    (net (code "90") (name "unconnected-(U1-PC15-Pad4)") (class "Default")
      (node (ref "U1") (pin "4") (pinfunction "PC15_4") (pintype "bidirectional"))
    )
    (net (code "91") (name "unconnected-(U2-TS-Pad4)") (class "Default")
      (node (ref "U2") (pin "4") (pinfunction "TS_4") (pintype "input"))
    )
    (net (code "92") (name "unconnected-(U3-NC-Pad5)") (class "Default")
      (node (ref "U3") (pin "5") (pinfunction "NC_5") (pintype "bidirectional"))
    )
    (net (code "93") (name "unconnected-(U3-NC-Pad6)") (class "Default")
      (node (ref "U3") (pin "6") (pinfunction "NC_6") (pintype "bidirectional"))
    )
    (net (code "94") (name "unconnected-(U3-NC-Pad10)") (class "Default")
      (node (ref "U3") (pin "10") (pinfunction "NC_10") (pintype "bidirectional"))
    )
    (net (code "95") (name "unconnected-(U3-NC-Pad16)") (class "Default")
      (node (ref "U3") (pin "16") (pinfunction "NC_16") (pintype "bidirectional"))
    )
    (net (code "96") (name "unconnected-(U3-NC-Pad17)") (class "Default")
      (node (ref "U3") (pin "17") (pinfunction "NC_17") (pintype "bidirectional"))
    )
    (net (code "97") (name "unconnected-(U3-NC-Pad18)") (class "Default")
      (node (ref "U3") (pin "18") (pinfunction "NC_18") (pintype "bidirectional"))
    )
    (net (code "98") (name "unconnected-(U3-NC-Pad19)") (class "Default")
      (node (ref "U3") (pin "19") (pinfunction "NC_19") (pintype "bidirectional"))
    )
    (net (code "99") (name "unconnected-(U3-P0_0-Pad34)") (class "Default")
      (node (ref "U3") (pin "34") (pinfunction "P0_0_34") (pintype "bidirectional"))
    )
    (net (code "100") (name "unconnected-(U3-P0_1-Pad33)") (class "Default")
      (node (ref "U3") (pin "33") (pinfunction "P0_1_33") (pintype "bidirectional"))
    )
    (net (code "101") (name "unconnected-(U3-P0_2-Pad32)") (class "Default")
      (node (ref "U3") (pin "32") (pinfunction "P0_2_32") (pintype "bidirectional"))
    )
    (net (code "102") (name "unconnected-(U3-P0_3-Pad31)") (class "Default")
      (node (ref "U3") (pin "31") (pinfunction "P0_3_31") (pintype "bidirectional"))
    )
    (net (code "103") (name "unconnected-(U3-P0_4-Pad30)") (class "Default")
      (node (ref "U3") (pin "30") (pinfunction "P0_4_30") (pintype "bidirectional"))
    )
    (net (code "104") (name "unconnected-(U3-P0_5-Pad29)") (class "Default")
      (node (ref "U3") (pin "29") (pinfunction "P0_5_29") (pintype "bidirectional"))
    )
    (net (code "105") (name "unconnected-(U3-P0_7-Pad27)") (class "Default")
      (node (ref "U3") (pin "27") (pinfunction "P0_7_27") (pintype "bidirectional"))
    )
    (net (code "106") (name "unconnected-(U3-P1_0-Pad26)") (class "Default")
      (node (ref "U3") (pin "26") (pinfunction "P1_0_26") (pintype "bidirectional"))
    )
    (net (code "107") (name "unconnected-(U3-P1_1-Pad25)") (class "Default")
      (node (ref "U3") (pin "25") (pinfunction "P1_1_25") (pintype "bidirectional"))
    )
    (net (code "108") (name "unconnected-(U3-P1_3-Pad23)") (class "Default")
      (node (ref "U3") (pin "23") (pinfunction "P1_3_23") (pintype "bidirectional"))
    )
    (net (code "109") (name "unconnected-(U3-P1_4-Pad3)") (class "Default")
      (node (ref "U3") (pin "3") (pinfunction "P1_4_3") (pintype "bidirectional"))
    )
    (net (code "110") (name "unconnected-(U3-P1_5-Pad4)") (class "Default")
      (node (ref "U3") (pin "4") (pinfunction "P1_5_4") (pintype "bidirectional"))
    )
    (net (code "111") (name "unconnected-(U3-P2_0-Pad9)") (class "Default")
      (node (ref "U3") (pin "9") (pinfunction "P2_0_9") (pintype "bidirectional"))
    )
    (net (code "112") (name "unconnected-(U3-P2_1-Pad8)") (class "Default")
      (node (ref "U3") (pin "8") (pinfunction "P2_1_8") (pintype "bidirectional"))
    )
    (net (code "113") (name "unconnected-(U3-P2_2-Pad7)") (class "Default")
      (node (ref "U3") (pin "7") (pinfunction "P2_2_7") (pintype "bidirectional"))
    )
    (net (code "114") (name "unconnected-(U3-RES-Pad11)") (class "Default")
      (node (ref "U3") (pin "11") (pinfunction "RES_11") (pintype "bidirectional"))
    )
    (net (code "115") (name "unconnected-(U3-USB_N-Pad15)") (class "Default")
      (node (ref "U3") (pin "15") (pinfunction "USB_N_15") (pintype "bidirectional"))
    )
    (net (code "116") (name "unconnected-(U3-USB_P-Pad20)") (class "Default")
      (node (ref "U3") (pin "20") (pinfunction "USB_P_20") (pintype "bidirectional"))
    )
    (net (code "117") (name "unconnected-(USB-PadID)") (class "Default")
      (node (ref "USB") (pin "ID") (pinfunction "ID_ID") (pintype "bidirectional"))
    )
  )
)
